# Sheet1.net
KiCad netlist of a schematic drawn in Altium Designer
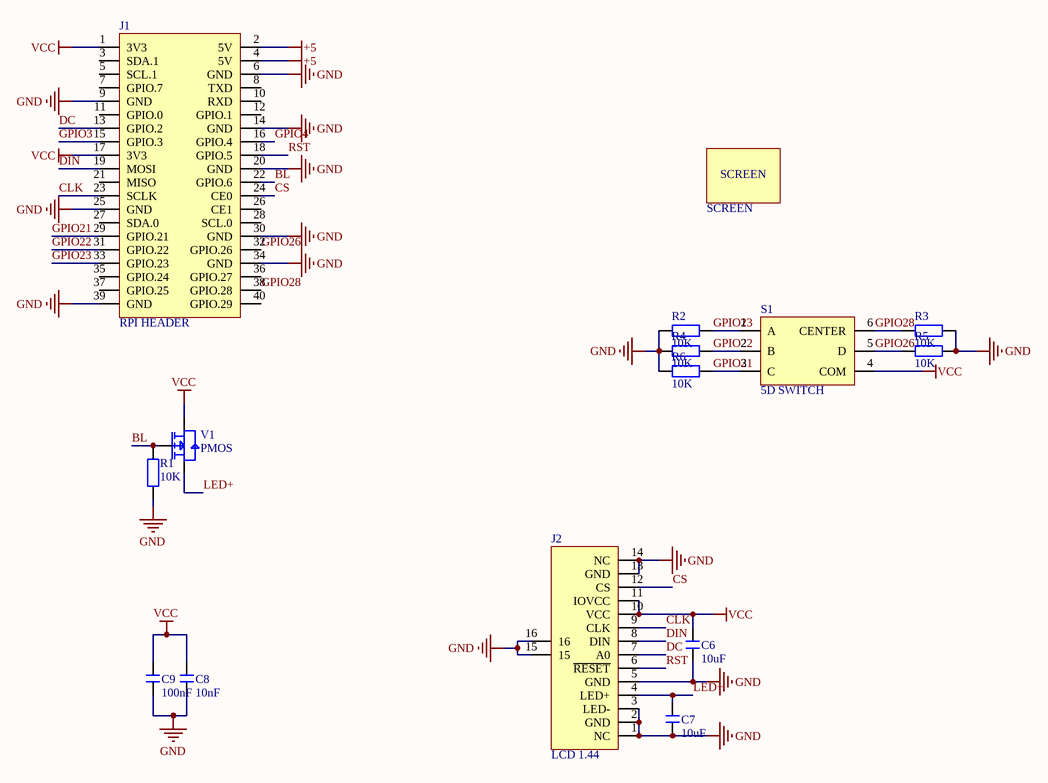
[diagram p0: Sheet1.SchDoc]

(export (version "E")
  (design (tool "Eeschema 10.0.6"))
  (components
    (comp (ref "C6")
      (value "10uF")
      (footprint "C 0603_M")
      (description "无极性贴片电容")
      (libsource (lib "元件库2") (part "C"))
    )
    (comp (ref "C7")
      (value "10uF")
      (footprint "C 0603_M")
      (description "无极性贴片电容")
      (libsource (lib "元件库2") (part "C"))
    )
    (comp (ref "C8")
      (value "10nF")
      (footprint "C 0603_M")
      (description "无极性贴片电容")
      (libsource (lib "元件库2") (part "C"))
    )
    (comp (ref "C9")
      (value "100nF")
      (footprint "C 0603_M")
      (description "无极性贴片电容")
      (libsource (lib "元件库2") (part "C"))
    )
    (comp (ref "J1")
      (value "RPI HEADER")
      (footprint "HEADER 2*20 SMD BACK")
      (libsource (lib "Schlib1") (part "RPI HEADER"))
    )
    (comp (ref "J2")
      (value "LCD 1.44")
      (footprint "FPC-14PIN-0.5")
      (libsource (lib "Schlib1") (part "LCD 1.44"))
    )
    (comp (ref "R1")
      (value "10K")
      (footprint "R 0603-HP")
      (description "贴片电阻")
      (fields (field (name "版权归属") "源创客"))
      (libsource (lib "Altium Designer 3D元件库") (part "R"))
    )
    (comp (ref "R2")
      (value "10K")
      (footprint "R 0603-HP")
      (description "贴片电阻")
      (fields (field (name "版权归属") "源创客"))
      (libsource (lib "Altium Designer 3D元件库") (part "R"))
    )
    (comp (ref "R3")
      (value "10K")
      (footprint "R 0603-HP")
      (description "贴片电阻")
      (fields (field (name "版权归属") "源创客"))
      (libsource (lib "Altium Designer 3D元件库") (part "R"))
    )
    (comp (ref "R4")
      (value "10K")
      (footprint "R 0603-HP")
      (description "贴片电阻")
      (fields (field (name "版权归属") "源创客"))
      (libsource (lib "Altium Designer 3D元件库") (part "R"))
    )
    (comp (ref "R5")
      (value "10K")
      (footprint "R 0603-HP")
      (description "贴片电阻")
      (fields (field (name "版权归属") "源创客"))
      (libsource (lib "Altium Designer 3D元件库") (part "R"))
    )
    (comp (ref "R6")
      (value "10K")
      (footprint "R 0603-HP")
      (description "贴片电阻")
      (fields (field (name "版权归属") "源创客"))
      (libsource (lib "Altium Designer 3D元件库") (part "R"))
    )
    (comp (ref "S1")
      (value "5D SWITCH")
      (footprint "5D SWITCH")
      (libsource (lib "Schlib1") (part "5D SWITCH"))
    )
    (comp (ref "S2") (value "SCREEN") (footprint "SCREEN") (libsource (lib "Schlib1") (part "SCREEN")))
    (comp (ref "V1") (value "PMOS") (footprint "SOT-23") (libsource (lib "Schlib1") (part "PMOS")))
  )
  (nets
    (net (code "1") (name "+5") (class "Default")
      (node (ref "J1") (pin "2") (pinfunction "5V_2") (pintype "passive"))
      (node (ref "J1") (pin "4") (pinfunction "5V_4") (pintype "passive"))
    )
    (net (code "2") (name "/BL") (class "Default")
      (node (ref "J1") (pin "22") (pinfunction "GPIO.6_22") (pintype "passive"))
      (node (ref "R1") (pin "1") (pinfunction "1_1") (pintype "passive"))
      (node (ref "V1") (pin "1") (pinfunction "G_1") (pintype "passive"))
    )
    (net (code "3") (name "/CLK") (class "Default")
      (node (ref "J1") (pin "23") (pinfunction "SCLK_23") (pintype "passive"))
      (node (ref "J2") (pin "9") (pinfunction "CLK_9") (pintype "passive"))
    )
    (net (code "4") (name "/CS") (class "Default")
      (node (ref "J1") (pin "24") (pinfunction "CE0_24") (pintype "passive"))
      (node (ref "J2") (pin "12") (pinfunction "CS_12") (pintype "passive"))
    )
    (net (code "5") (name "/DC") (class "Default")
      (node (ref "J1") (pin "13") (pinfunction "GPIO.2_13") (pintype "passive"))
      (node (ref "J2") (pin "7") (pinfunction "A0_7") (pintype "passive"))
    )
    (net (code "6") (name "/DIN") (class "Default")
      (node (ref "J1") (pin "19") (pinfunction "MOSI_19") (pintype "passive"))
      (node (ref "J2") (pin "8") (pinfunction "DIN_8") (pintype "passive"))
    )
    (net (code "7") (name "/GPIO3") (class "Default")
      (node (ref "J1") (pin "15") (pinfunction "GPIO.3_15") (pintype "passive"))
    )
    (net (code "8") (name "/GPIO4") (class "Default")
      (node (ref "J1") (pin "16") (pinfunction "GPIO.4_16") (pintype "passive"))
    )
    (net (code "9") (name "/GPIO21") (class "Default")
      (node (ref "J1") (pin "29") (pinfunction "GPIO.21_29") (pintype "passive"))
      (node (ref "R6") (pin "2") (pinfunction "2_2") (pintype "passive"))
      (node (ref "S1") (pin "3") (pinfunction "C_3") (pintype "passive"))
    )
    (net (code "10") (name "/GPIO22") (class "Default")
      (node (ref "J1") (pin "31") (pinfunction "GPIO.22_31") (pintype "passive"))
      (node (ref "R4") (pin "2") (pinfunction "2_2") (pintype "passive"))
      (node (ref "S1") (pin "2") (pinfunction "B_2") (pintype "passive"))
    )
    (net (code "11") (name "/GPIO23") (class "Default")
      (node (ref "J1") (pin "33") (pinfunction "GPIO.23_33") (pintype "passive"))
      (node (ref "R2") (pin "2") (pinfunction "2_2") (pintype "passive"))
      (node (ref "S1") (pin "1") (pinfunction "A_1") (pintype "passive"))
    )
    (net (code "12") (name "/GPIO26") (class "Default")
      (node (ref "J1") (pin "32") (pinfunction "GPIO.26_32") (pintype "passive"))
      (node (ref "R5") (pin "1") (pinfunction "1_1") (pintype "passive"))
      (node (ref "S1") (pin "5") (pinfunction "D_5") (pintype "passive"))
    )
    (net (code "13") (name "/GPIO28") (class "Default")
      (node (ref "J1") (pin "38") (pinfunction "GPIO.28_38") (pintype "passive"))
      (node (ref "R3") (pin "1") (pinfunction "1_1") (pintype "passive"))
      (node (ref "S1") (pin "6") (pinfunction "CENTER_6") (pintype "passive"))
    )
    (net (code "14") (name "/LED+") (class "Default")
      (node (ref "C7") (pin "1") (pinfunction "1_1") (pintype "passive"))
      (node (ref "J2") (pin "4") (pinfunction "LED+_4") (pintype "passive"))
      (node (ref "V1") (pin "3") (pinfunction "D_3") (pintype "passive"))
    )
    (net (code "15") (name "/RST") (class "Default")
      (node (ref "J1") (pin "18") (pinfunction "GPIO.5_18") (pintype "passive"))
      (node (ref "J2") (pin "6") (pinfunction "~{RESET}_6") (pintype "passive"))
    )
    (net (code "16") (name "GND") (class "Default")
      (node (ref "C6") (pin "1") (pinfunction "1_1") (pintype "passive"))
      (node (ref "C7") (pin "2") (pinfunction "2_2") (pintype "passive"))
      (node (ref "C8") (pin "1") (pinfunction "1_1") (pintype "passive"))
      (node (ref "C9") (pin "1") (pinfunction "1_1") (pintype "passive"))
      (node (ref "J1") (pin "14") (pinfunction "GND_14") (pintype "passive"))
      (node (ref "J1") (pin "20") (pinfunction "GND_20") (pintype "passive"))
      (node (ref "J1") (pin "25") (pinfunction "GND_25") (pintype "passive"))
      (node (ref "J1") (pin "30") (pinfunction "GND_30") (pintype "passive"))
      (node (ref "J1") (pin "34") (pinfunction "GND_34") (pintype "passive"))
      (node (ref "J1") (pin "39") (pinfunction "GND_39") (pintype "passive"))
      (node (ref "J1") (pin "6") (pinfunction "GND_6") (pintype "passive"))
      (node (ref "J1") (pin "9") (pinfunction "GND_9") (pintype "passive"))
      (node (ref "J2") (pin "1") (pinfunction "NC_1") (pintype "passive"))
      (node (ref "J2") (pin "13") (pinfunction "GND_13") (pintype "passive"))
      (node (ref "J2") (pin "14") (pinfunction "NC_14") (pintype "passive"))
      (node (ref "J2") (pin "15") (pinfunction "15_15") (pintype "passive"))
      (node (ref "J2") (pin "16") (pinfunction "16_16") (pintype "passive"))
      (node (ref "J2") (pin "2") (pinfunction "GND_2") (pintype "passive"))
      (node (ref "J2") (pin "3") (pinfunction "LED-_3") (pintype "passive"))
      (node (ref "J2") (pin "5") (pinfunction "GND_5") (pintype "passive"))
      (node (ref "R1") (pin "2") (pinfunction "2_2") (pintype "passive"))
      (node (ref "R2") (pin "1") (pinfunction "1_1") (pintype "passive"))
      (node (ref "R3") (pin "2") (pinfunction "2_2") (pintype "passive"))
      (node (ref "R4") (pin "1") (pinfunction "1_1") (pintype "passive"))
      (node (ref "R5") (pin "2") (pinfunction "2_2") (pintype "passive"))
      (node (ref "R6") (pin "1") (pinfunction "1_1") (pintype "passive"))
    )
    (net (code "17") (name "VCC") (class "Default")
      (node (ref "C6") (pin "2") (pinfunction "2_2") (pintype "passive"))
      (node (ref "C8") (pin "2") (pinfunction "2_2") (pintype "passive"))
      (node (ref "C9") (pin "2") (pinfunction "2_2") (pintype "passive"))
      (node (ref "J1") (pin "1") (pinfunction "3V3_1") (pintype "power_in"))
      (node (ref "J1") (pin "17") (pinfunction "3V3_17") (pintype "passive"))
      (node (ref "J2") (pin "10") (pinfunction "VCC_10") (pintype "passive"))
      (node (ref "J2") (pin "11") (pinfunction "IOVCC_11") (pintype "passive"))
      (node (ref "S1") (pin "4") (pinfunction "COM_4") (pintype "passive"))
      (node (ref "V1") (pin "2") (pinfunction "S_2") (pintype "passive"))
    )
    (net (code "18") (name "unconnected-(J1-CE1-Pad26)") (class "Default")
      (node (ref "J1") (pin "26") (pinfunction "CE1_26") (pintype "passive"))
    )
    (net (code "19") (name "unconnected-(J1-GPIO.0-Pad11)") (class "Default")
      (node (ref "J1") (pin "11") (pinfunction "GPIO.0_11") (pintype "passive"))
    )
    (net (code "20") (name "unconnected-(J1-GPIO.1-Pad12)") (class "Default")
      (node (ref "J1") (pin "12") (pinfunction "GPIO.1_12") (pintype "passive"))
    )
    (net (code "21") (name "unconnected-(J1-GPIO.7-Pad7)") (class "Default")
      (node (ref "J1") (pin "7") (pinfunction "GPIO.7_7") (pintype "passive"))
    )
    (net (code "22") (name "unconnected-(J1-GPIO.24-Pad35)") (class "Default")
      (node (ref "J1") (pin "35") (pinfunction "GPIO.24_35") (pintype "passive"))
    )
    (net (code "23") (name "unconnected-(J1-GPIO.25-Pad37)") (class "Default")
      (node (ref "J1") (pin "37") (pinfunction "GPIO.25_37") (pintype "passive"))
    )
    (net (code "24") (name "unconnected-(J1-GPIO.27-Pad36)") (class "Default")
      (node (ref "J1") (pin "36") (pinfunction "GPIO.27_36") (pintype "passive"))
    )
    (net (code "25") (name "unconnected-(J1-GPIO.29-Pad40)") (class "Default")
      (node (ref "J1") (pin "40") (pinfunction "GPIO.29_40") (pintype "passive"))
    )
    (net (code "26") (name "unconnected-(J1-MISO-Pad21)") (class "Default")
      (node (ref "J1") (pin "21") (pinfunction "MISO_21") (pintype "passive"))
    )
    (net (code "27") (name "unconnected-(J1-RXD-Pad10)") (class "Default")
      (node (ref "J1") (pin "10") (pinfunction "RXD_10") (pintype "passive"))
    )
    (net (code "28") (name "unconnected-(J1-SCL.0-Pad28)") (class "Default")
      (node (ref "J1") (pin "28") (pinfunction "SCL.0_28") (pintype "passive"))
    )
    (net (code "29") (name "unconnected-(J1-SCL.1-Pad5)") (class "Default")
      (node (ref "J1") (pin "5") (pinfunction "SCL.1_5") (pintype "passive"))
    )
    (net (code "30") (name "unconnected-(J1-SDA.0-Pad27)") (class "Default")
      (node (ref "J1") (pin "27") (pinfunction "SDA.0_27") (pintype "passive"))
    )
    (net (code "31") (name "unconnected-(J1-SDA.1-Pad3)") (class "Default")
      (node (ref "J1") (pin "3") (pinfunction "SDA.1_3") (pintype "passive"))
    )
    (net (code "32") (name "unconnected-(J1-TXD-Pad8)") (class "Default")
      (node (ref "J1") (pin "8") (pinfunction "TXD_8") (pintype "passive"))
    )
  )
)
